# 2_LPC1850__P5-PA.net
KiCad netlist of a schematic drawn in Altium Designer
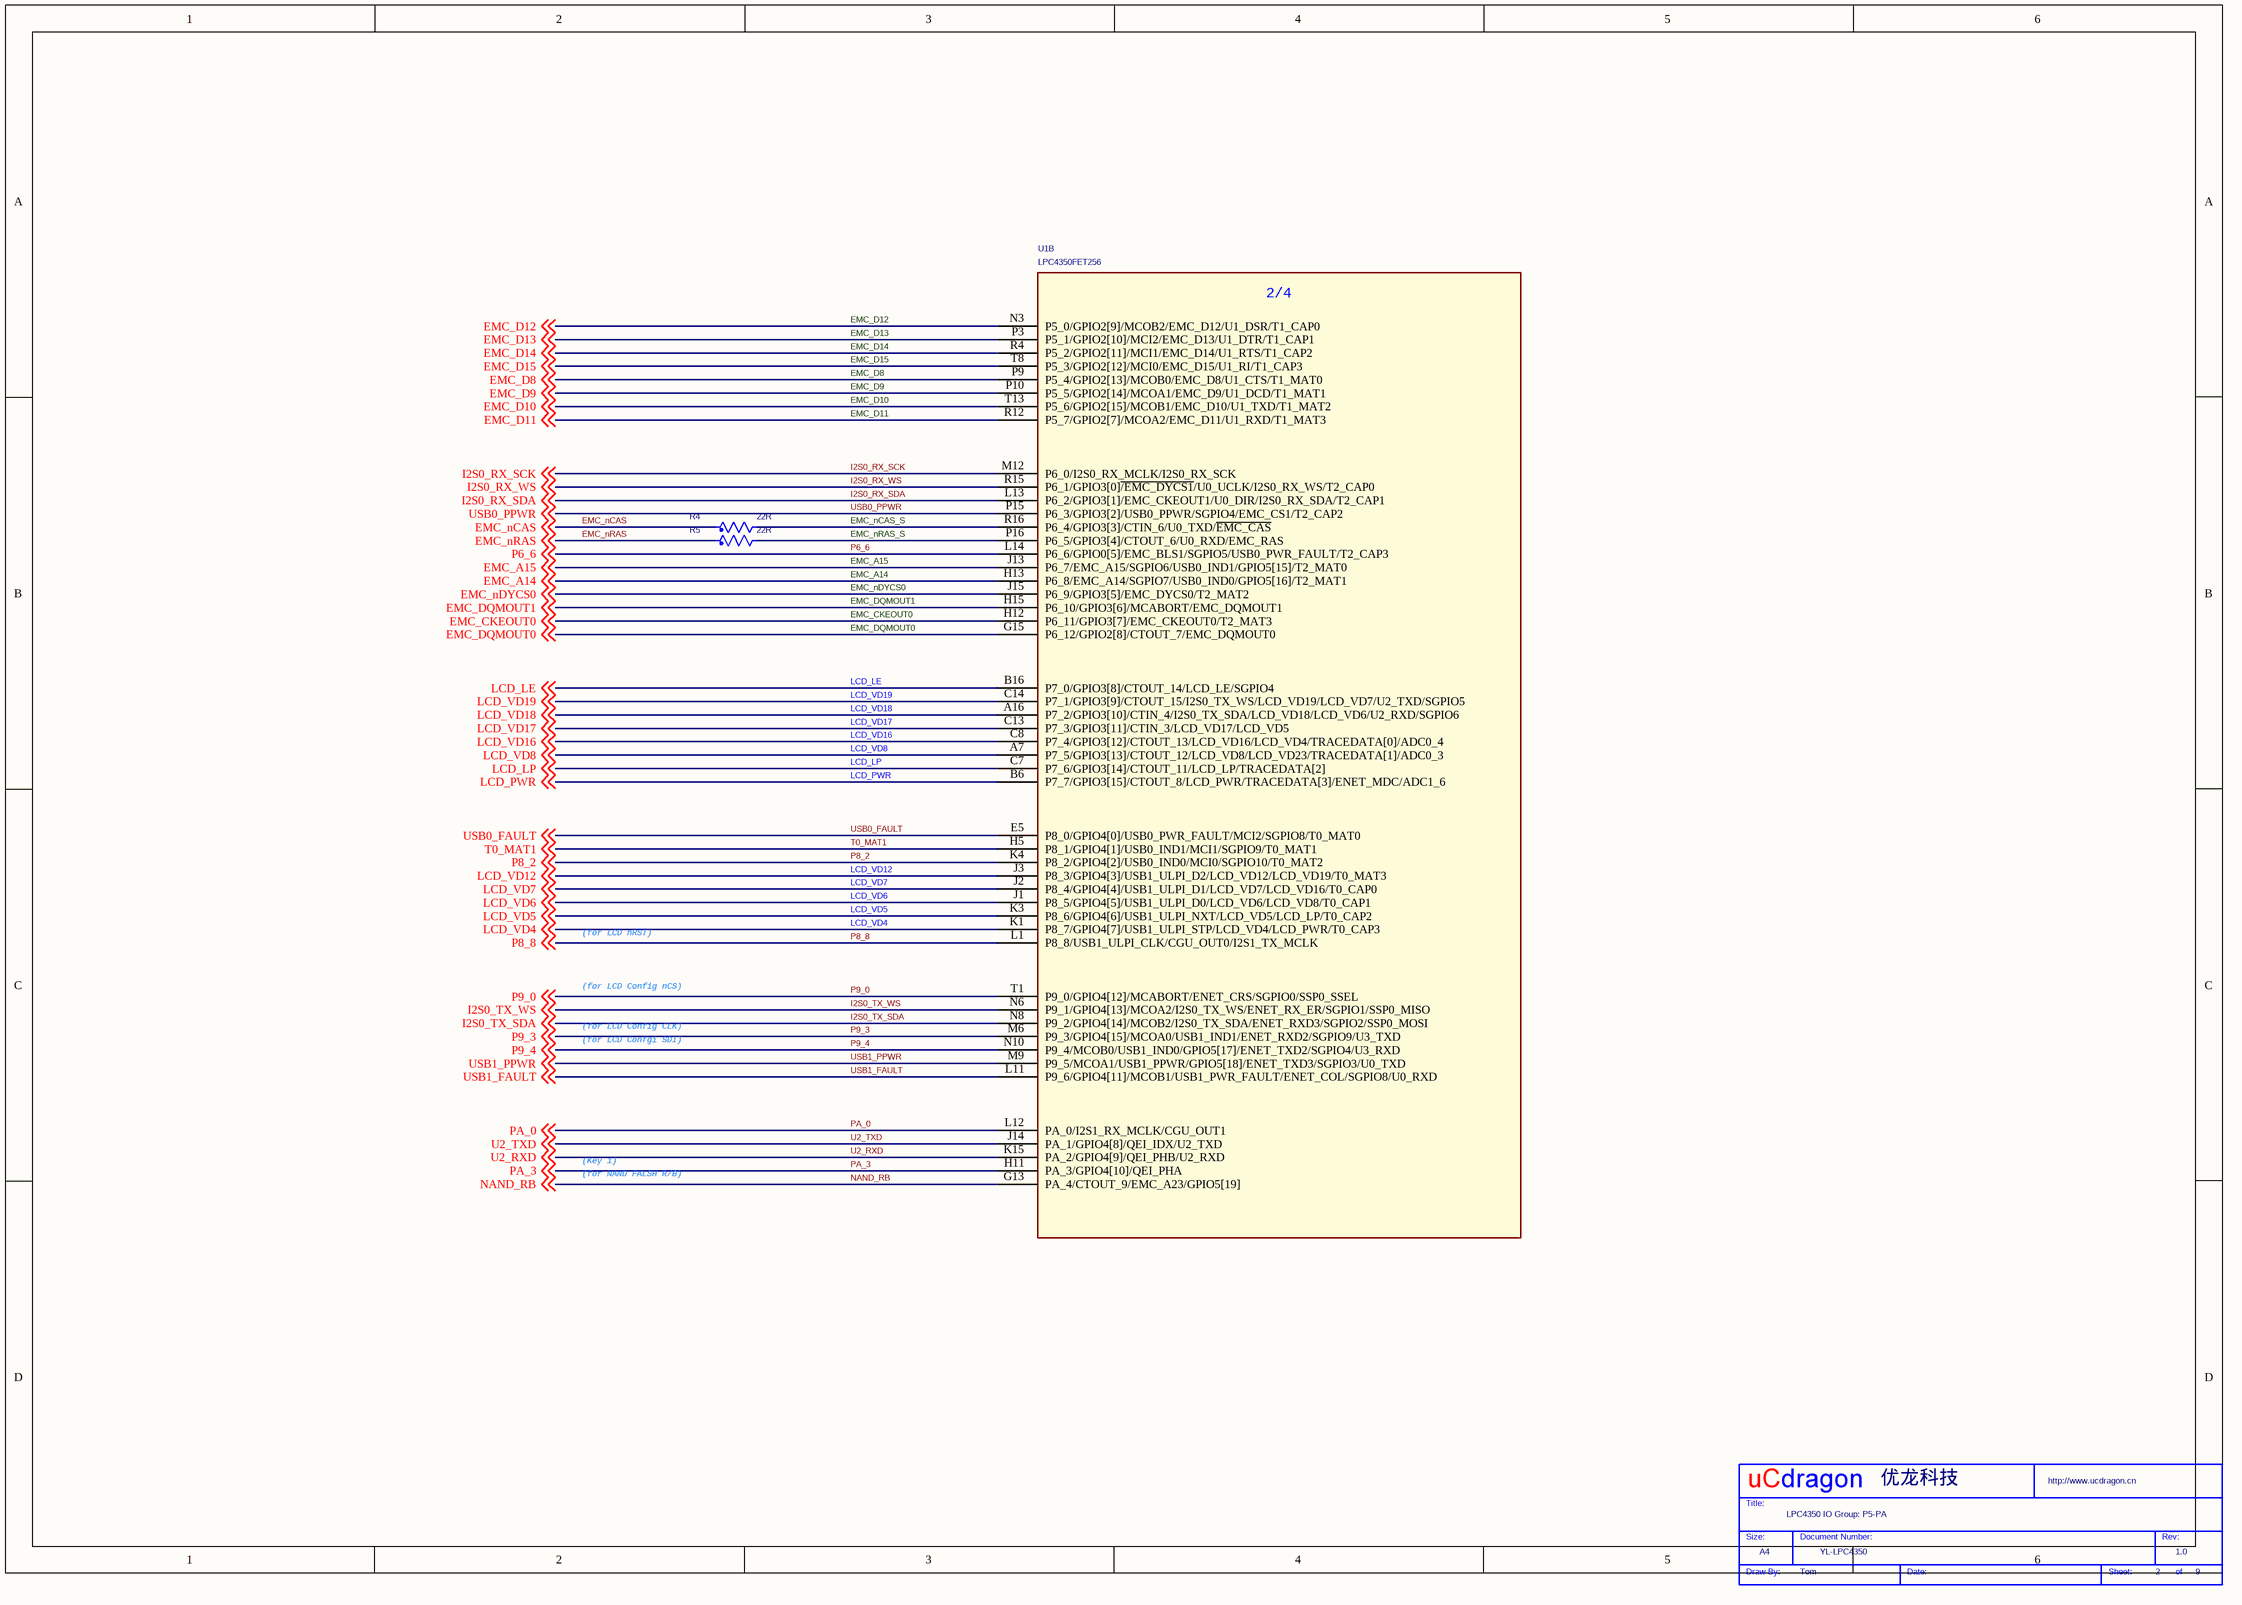
[diagram p0: 2) LPC1850_ P5-PA.SchDoc]

(export (version "E")
  (design (tool "Eeschema 10.0.6"))
  (components
    (comp (ref "*")
      (value "My Title 0")
      (fields
        (field (name "COMPANY") "优龙科技")
        (field (name "DRAWING") "Tom")
        (field (name "WEBSITE") "http://www.ucdragon.cn")
        (field (name "DOC") "YL-LPC4350")
        (field (name "REVCODE") "1.0")
        (field (name "TITLE") "LPC4350 IO Group: P5-PA")
        (field (name "PAGE SIZE") "A4")
        (field (name "PAGE NUMBER") "2")
        (field (name "PAGE COUNT") "9")
      )
      (libsource (lib "*") (part "My Title 0"))
    )
    (comp (ref "R4") (value "22R") (libsource (lib "*") (part "R_Generic_Dup2")))
    (comp (ref "R5") (value "22R") (libsource (lib "*") (part "R_Generic_Dup2")))
    (comp (ref "U1")
      (value "LPC4350FET256")
      (footprint "LBGA256")
      (libsource (lib "*") (part "LPC4350FET256"))
    )
  )
  (nets
    (net (code "1") (name "/EMC_nCAS_S") (class "Default")
      (node (ref "R4") (pin "2") (pinfunction "2_2") (pintype "passive"))
      (node (ref "U1") (pin "R16") (pinfunction "P6_4/GPIO3[3]/CTIN_6/U0_TXD/~{EMC_CAS}_R16") (pintype "passive"))
    )
    (net (code "2") (name "/EMC_nRAS_S") (class "Default")
      (node (ref "R5") (pin "2") (pinfunction "2_2") (pintype "passive"))
      (node (ref "U1") (pin "P16") (pinfunction "P6_5/GPIO3[4]/CTOUT_6/U0_RXD/EMC_RAS_P16") (pintype "passive"))
    )
    (net (code "3") (name "EMC_A14") (class "Default")
      (node (ref "U1") (pin "H13") (pinfunction "P6_8/EMC_A14/SGPIO7/USB0_IND0/GPIO5[16]/T2_MAT1_H13") (pintype "passive"))
    )
    (net (code "4") (name "EMC_A15") (class "Default")
      (node (ref "U1") (pin "J13") (pinfunction "P6_7/EMC_A15/SGPIO6/USB0_IND1/GPIO5[15]/T2_MAT0_J13") (pintype "passive"))
    )
    (net (code "5") (name "EMC_CKEOUT0") (class "Default")
      (node (ref "U1") (pin "H12") (pinfunction "P6_11/GPIO3[7]/EMC_CKEOUT0/T2_MAT3_H12") (pintype "passive"))
    )
    (net (code "6") (name "EMC_D8") (class "Default")
      (node (ref "U1") (pin "P9") (pinfunction "P5_4/GPIO2[13]/MCOB0/EMC_D8/U1_CTS/T1_MAT0_P9") (pintype "passive"))
    )
    (net (code "7") (name "EMC_D9") (class "Default")
      (node (ref "U1") (pin "P10") (pinfunction "P5_5/GPIO2[14]/MCOA1/EMC_D9/U1_DCD/T1_MAT1_P10") (pintype "passive"))
    )
    (net (code "8") (name "EMC_D10") (class "Default")
      (node (ref "U1") (pin "T13") (pinfunction "P5_6/GPIO2[15]/MCOB1/EMC_D10/U1_TXD/T1_MAT2_T13") (pintype "passive"))
    )
    (net (code "9") (name "EMC_D11") (class "Default")
      (node (ref "U1") (pin "R12") (pinfunction "P5_7/GPIO2[7]/MCOA2/EMC_D11/U1_RXD/T1_MAT3_R12") (pintype "passive"))
    )
    (net (code "10") (name "EMC_D12") (class "Default")
      (node (ref "U1") (pin "N3") (pinfunction "P5_0/GPIO2[9]/MCOB2/EMC_D12/U1_DSR/T1_CAP0_N3") (pintype "passive"))
    )
    (net (code "11") (name "EMC_D13") (class "Default")
      (node (ref "U1") (pin "P3") (pinfunction "P5_1/GPIO2[10]/MCI2/EMC_D13/U1_DTR/T1_CAP1_P3") (pintype "passive"))
    )
    (net (code "12") (name "EMC_D14") (class "Default")
      (node (ref "U1") (pin "R4") (pinfunction "P5_2/GPIO2[11]/MCI1/EMC_D14/U1_RTS/T1_CAP2_R4") (pintype "passive"))
    )
    (net (code "13") (name "EMC_D15") (class "Default")
      (node (ref "U1") (pin "T8") (pinfunction "P5_3/GPIO2[12]/MCI0/EMC_D15/U1_RI/T1_CAP3_T8") (pintype "passive"))
    )
    (net (code "14") (name "EMC_DQMOUT0") (class "Default")
      (node (ref "U1") (pin "G15") (pinfunction "P6_12/GPIO2[8]/CTOUT_7/EMC_DQMOUT0_G15") (pintype "passive"))
    )
    (net (code "15") (name "EMC_DQMOUT1") (class "Default")
      (node (ref "U1") (pin "H15") (pinfunction "P6_10/GPIO3[6]/MCABORT/EMC_DQMOUT1_H15") (pintype "passive"))
    )
    (net (code "16") (name "EMC_nCAS") (class "Default")
      (node (ref "R4") (pin "1") (pinfunction "1_1") (pintype "passive"))
    )
    (net (code "17") (name "EMC_nDYCS0") (class "Default")
      (node (ref "U1") (pin "J15") (pinfunction "P6_9/GPIO3[5]/EMC_DYCS0/T2_MAT2_J15") (pintype "passive"))
    )
    (net (code "18") (name "EMC_nRAS") (class "Default")
      (node (ref "R5") (pin "1") (pinfunction "1_1") (pintype "passive"))
    )
    (net (code "19") (name "I2S0_RX_SCK") (class "Default")
      (node (ref "U1") (pin "M12") (pinfunction "P6_0/I2S0_RX_MCLK/I2S0_RX_SCK_M12") (pintype "passive"))
    )
    (net (code "20") (name "I2S0_RX_SDA") (class "Default")
      (node (ref "U1") (pin "L13") (pinfunction "P6_2/GPIO3[1]/EMC_CKEOUT1/U0_DIR/I2S0_RX_SDA/T2_CAP1_L13") (pintype "passive"))
    )
    (net (code "21") (name "I2S0_RX_WS") (class "Default")
      (node (ref "U1") (pin "R15") (pinfunction "P6_1/GPIO3[0]~{/EMC_DYCS1}/U0_UCLK/I2S0_RX_WS/T2_CAP0_R15") (pintype "passive"))
    )
    (net (code "22") (name "I2S0_TX_SDA") (class "Default")
      (node (ref "U1") (pin "N8") (pinfunction "P9_2/GPIO4[14]/MCOB2/I2S0_TX_SDA/ENET_RXD3/SGPIO2/SSP0_MOSI_N8") (pintype "passive"))
    )
    (net (code "23") (name "I2S0_TX_WS") (class "Default")
      (node (ref "U1") (pin "N6") (pinfunction "P9_1/GPIO4[13]/MCOA2/I2S0_TX_WS/ENET_RX_ER/SGPIO1/SSP0_MISO_N6") (pintype "passive"))
    )
    (net (code "24") (name "LCD_LE") (class "Default")
      (node (ref "U1") (pin "B16") (pinfunction "P7_0/GPIO3[8]/CTOUT_14/LCD_LE/SGPIO4_B16") (pintype "passive"))
    )
    (net (code "25") (name "LCD_LP") (class "Default")
      (node (ref "U1") (pin "C7") (pinfunction "P7_6/GPIO3[14]/CTOUT_11/LCD_LP/TRACEDATA[2]_C7") (pintype "passive"))
    )
    (net (code "26") (name "LCD_PWR") (class "Default")
      (node (ref "U1") (pin "B6") (pinfunction "P7_7/GPIO3[15]/CTOUT_8/LCD_PWR/TRACEDATA[3]/ENET_MDC/ADC1_6_B6") (pintype "passive"))
    )
    (net (code "27") (name "LCD_VD4") (class "Default")
      (node (ref "U1") (pin "K1") (pinfunction "P8_7/GPIO4[7]/USB1_ULPI_STP/LCD_VD4/LCD_PWR/T0_CAP3_K1") (pintype "passive"))
    )
    (net (code "28") (name "LCD_VD5") (class "Default")
      (node (ref "U1") (pin "K3") (pinfunction "P8_6/GPIO4[6]/USB1_ULPI_NXT/LCD_VD5/LCD_LP/T0_CAP2_K3") (pintype "passive"))
    )
    (net (code "29") (name "LCD_VD6") (class "Default")
      (node (ref "U1") (pin "J1") (pinfunction "P8_5/GPIO4[5]/USB1_ULPI_D0/LCD_VD6/LCD_VD8/T0_CAP1_J1") (pintype "passive"))
    )
    (net (code "30") (name "LCD_VD7") (class "Default")
      (node (ref "U1") (pin "J2") (pinfunction "P8_4/GPIO4[4]/USB1_ULPI_D1/LCD_VD7/LCD_VD16/T0_CAP0_J2") (pintype "passive"))
    )
    (net (code "31") (name "LCD_VD8") (class "Default")
      (node (ref "U1") (pin "A7") (pinfunction "P7_5/GPIO3[13]/CTOUT_12/LCD_VD8/LCD_VD23/TRACEDATA[1]/ADC0_3_A7") (pintype "passive"))
    )
    (net (code "32") (name "LCD_VD12") (class "Default")
      (node (ref "U1") (pin "J3") (pinfunction "P8_3/GPIO4[3]/USB1_ULPI_D2/LCD_VD12/LCD_VD19/T0_MAT3_J3") (pintype "passive"))
    )
    (net (code "33") (name "LCD_VD16") (class "Default")
      (node (ref "U1") (pin "C8") (pinfunction "P7_4/GPIO3[12]/CTOUT_13/LCD_VD16/LCD_VD4/TRACEDATA[0]/ADC0_4_C8") (pintype "passive"))
    )
    (net (code "34") (name "LCD_VD17") (class "Default")
      (node (ref "U1") (pin "C13") (pinfunction "P7_3/GPIO3[11]/CTIN_3/LCD_VD17/LCD_VD5_C13") (pintype "passive"))
    )
    (net (code "35") (name "LCD_VD18") (class "Default")
      (node (ref "U1") (pin "A16") (pinfunction "P7_2/GPIO3[10]/CTIN_4/I2S0_TX_SDA/LCD_VD18/LCD_VD6/U2_RXD/SGPIO6_A16") (pintype "passive"))
    )
    (net (code "36") (name "LCD_VD19") (class "Default")
      (node (ref "U1") (pin "C14") (pinfunction "P7_1/GPIO3[9]/CTOUT_15/I2S0_TX_WS/LCD_VD19/LCD_VD7/U2_TXD/SGPIO5_C14") (pintype "passive"))
    )
    (net (code "37") (name "NAND_RB") (class "Default")
      (node (ref "U1") (pin "G13") (pinfunction "PA_4/CTOUT_9/EMC_A23/GPIO5[19]_G13") (pintype "passive"))
    )
    (net (code "38") (name "P6_6") (class "Default")
      (node (ref "U1") (pin "L14") (pinfunction "P6_6/GPIO0[5]/EMC_BLS1/SGPIO5/USB0_PWR_FAULT/T2_CAP3_L14") (pintype "passive"))
    )
    (net (code "39") (name "P8_2") (class "Default")
      (node (ref "U1") (pin "K4") (pinfunction "P8_2/GPIO4[2]/USB0_IND0/MCI0/SGPIO10/T0_MAT2_K4") (pintype "passive"))
    )
    (net (code "40") (name "P8_8") (class "Default")
      (node (ref "U1") (pin "L1") (pinfunction "P8_8/USB1_ULPI_CLK/CGU_OUT0/I2S1_TX_MCLK_L1") (pintype "passive"))
    )
    (net (code "41") (name "P9_0") (class "Default")
      (node (ref "U1") (pin "T1") (pinfunction "P9_0/GPIO4[12]/MCABORT/ENET_CRS/SGPIO0/SSP0_SSEL_T1") (pintype "passive"))
    )
    (net (code "42") (name "P9_3") (class "Default")
      (node (ref "U1") (pin "M6") (pinfunction "P9_3/GPIO4[15]/MCOA0/USB1_IND1/ENET_RXD2/SGPIO9/U3_TXD_M6") (pintype "passive"))
    )
    (net (code "43") (name "P9_4") (class "Default")
      (node (ref "U1") (pin "N10") (pinfunction "P9_4/MCOB0/USB1_IND0/GPIO5[17]/ENET_TXD2/SGPIO4/U3_RXD_N10") (pintype "passive"))
    )
    (net (code "44") (name "PA_0") (class "Default")
      (node (ref "U1") (pin "L12") (pinfunction "PA_0/I2S1_RX_MCLK/CGU_OUT1_L12") (pintype "passive"))
    )
    (net (code "45") (name "PA_3") (class "Default")
      (node (ref "U1") (pin "H11") (pinfunction "PA_3/GPIO4[10]/QEI_PHA_H11") (pintype "passive"))
    )
    (net (code "46") (name "T0_MAT1") (class "Default")
      (node (ref "U1") (pin "H5") (pinfunction "P8_1/GPIO4[1]/USB0_IND1/MCI1/SGPIO9/T0_MAT1_H5") (pintype "passive"))
    )
    (net (code "47") (name "U2_RXD") (class "Default")
      (node (ref "U1") (pin "K15") (pinfunction "PA_2/GPIO4[9]/QEI_PHB/U2_RXD_K15") (pintype "passive"))
    )
    (net (code "48") (name "U2_TXD") (class "Default")
      (node (ref "U1") (pin "J14") (pinfunction "PA_1/GPIO4[8]/QEI_IDX/U2_TXD_J14") (pintype "passive"))
    )
    (net (code "49") (name "USB0_FAULT") (class "Default")
      (node (ref "U1") (pin "E5") (pinfunction "P8_0/GPIO4[0]/USB0_PWR_FAULT/MCI2/SGPIO8/T0_MAT0_E5") (pintype "passive"))
    )
    (net (code "50") (name "USB0_PPWR") (class "Default")
      (node (ref "U1") (pin "P15") (pinfunction "P6_3/GPIO3[2]/USB0_PPWR/SGPIO4/EMC_CS1/T2_CAP2_P15") (pintype "passive"))
    )
    (net (code "51") (name "USB1_FAULT") (class "Default")
      (node (ref "U1") (pin "L11") (pinfunction "P9_6/GPIO4[11]/MCOB1/USB1_PWR_FAULT/ENET_COL/SGPIO8/U0_RXD_L11") (pintype "passive"))
    )
    (net (code "52") (name "USB1_PPWR") (class "Default")
      (node (ref "U1") (pin "M9") (pinfunction "P9_5/MCOA1/USB1_PPWR/GPIO5[18]/ENET_TXD3/SGPIO3/U0_TXD_M9") (pintype "passive"))
    )
  )
)
